# Master.net
KiCad netlist of a schematic drawn in Altium Designer
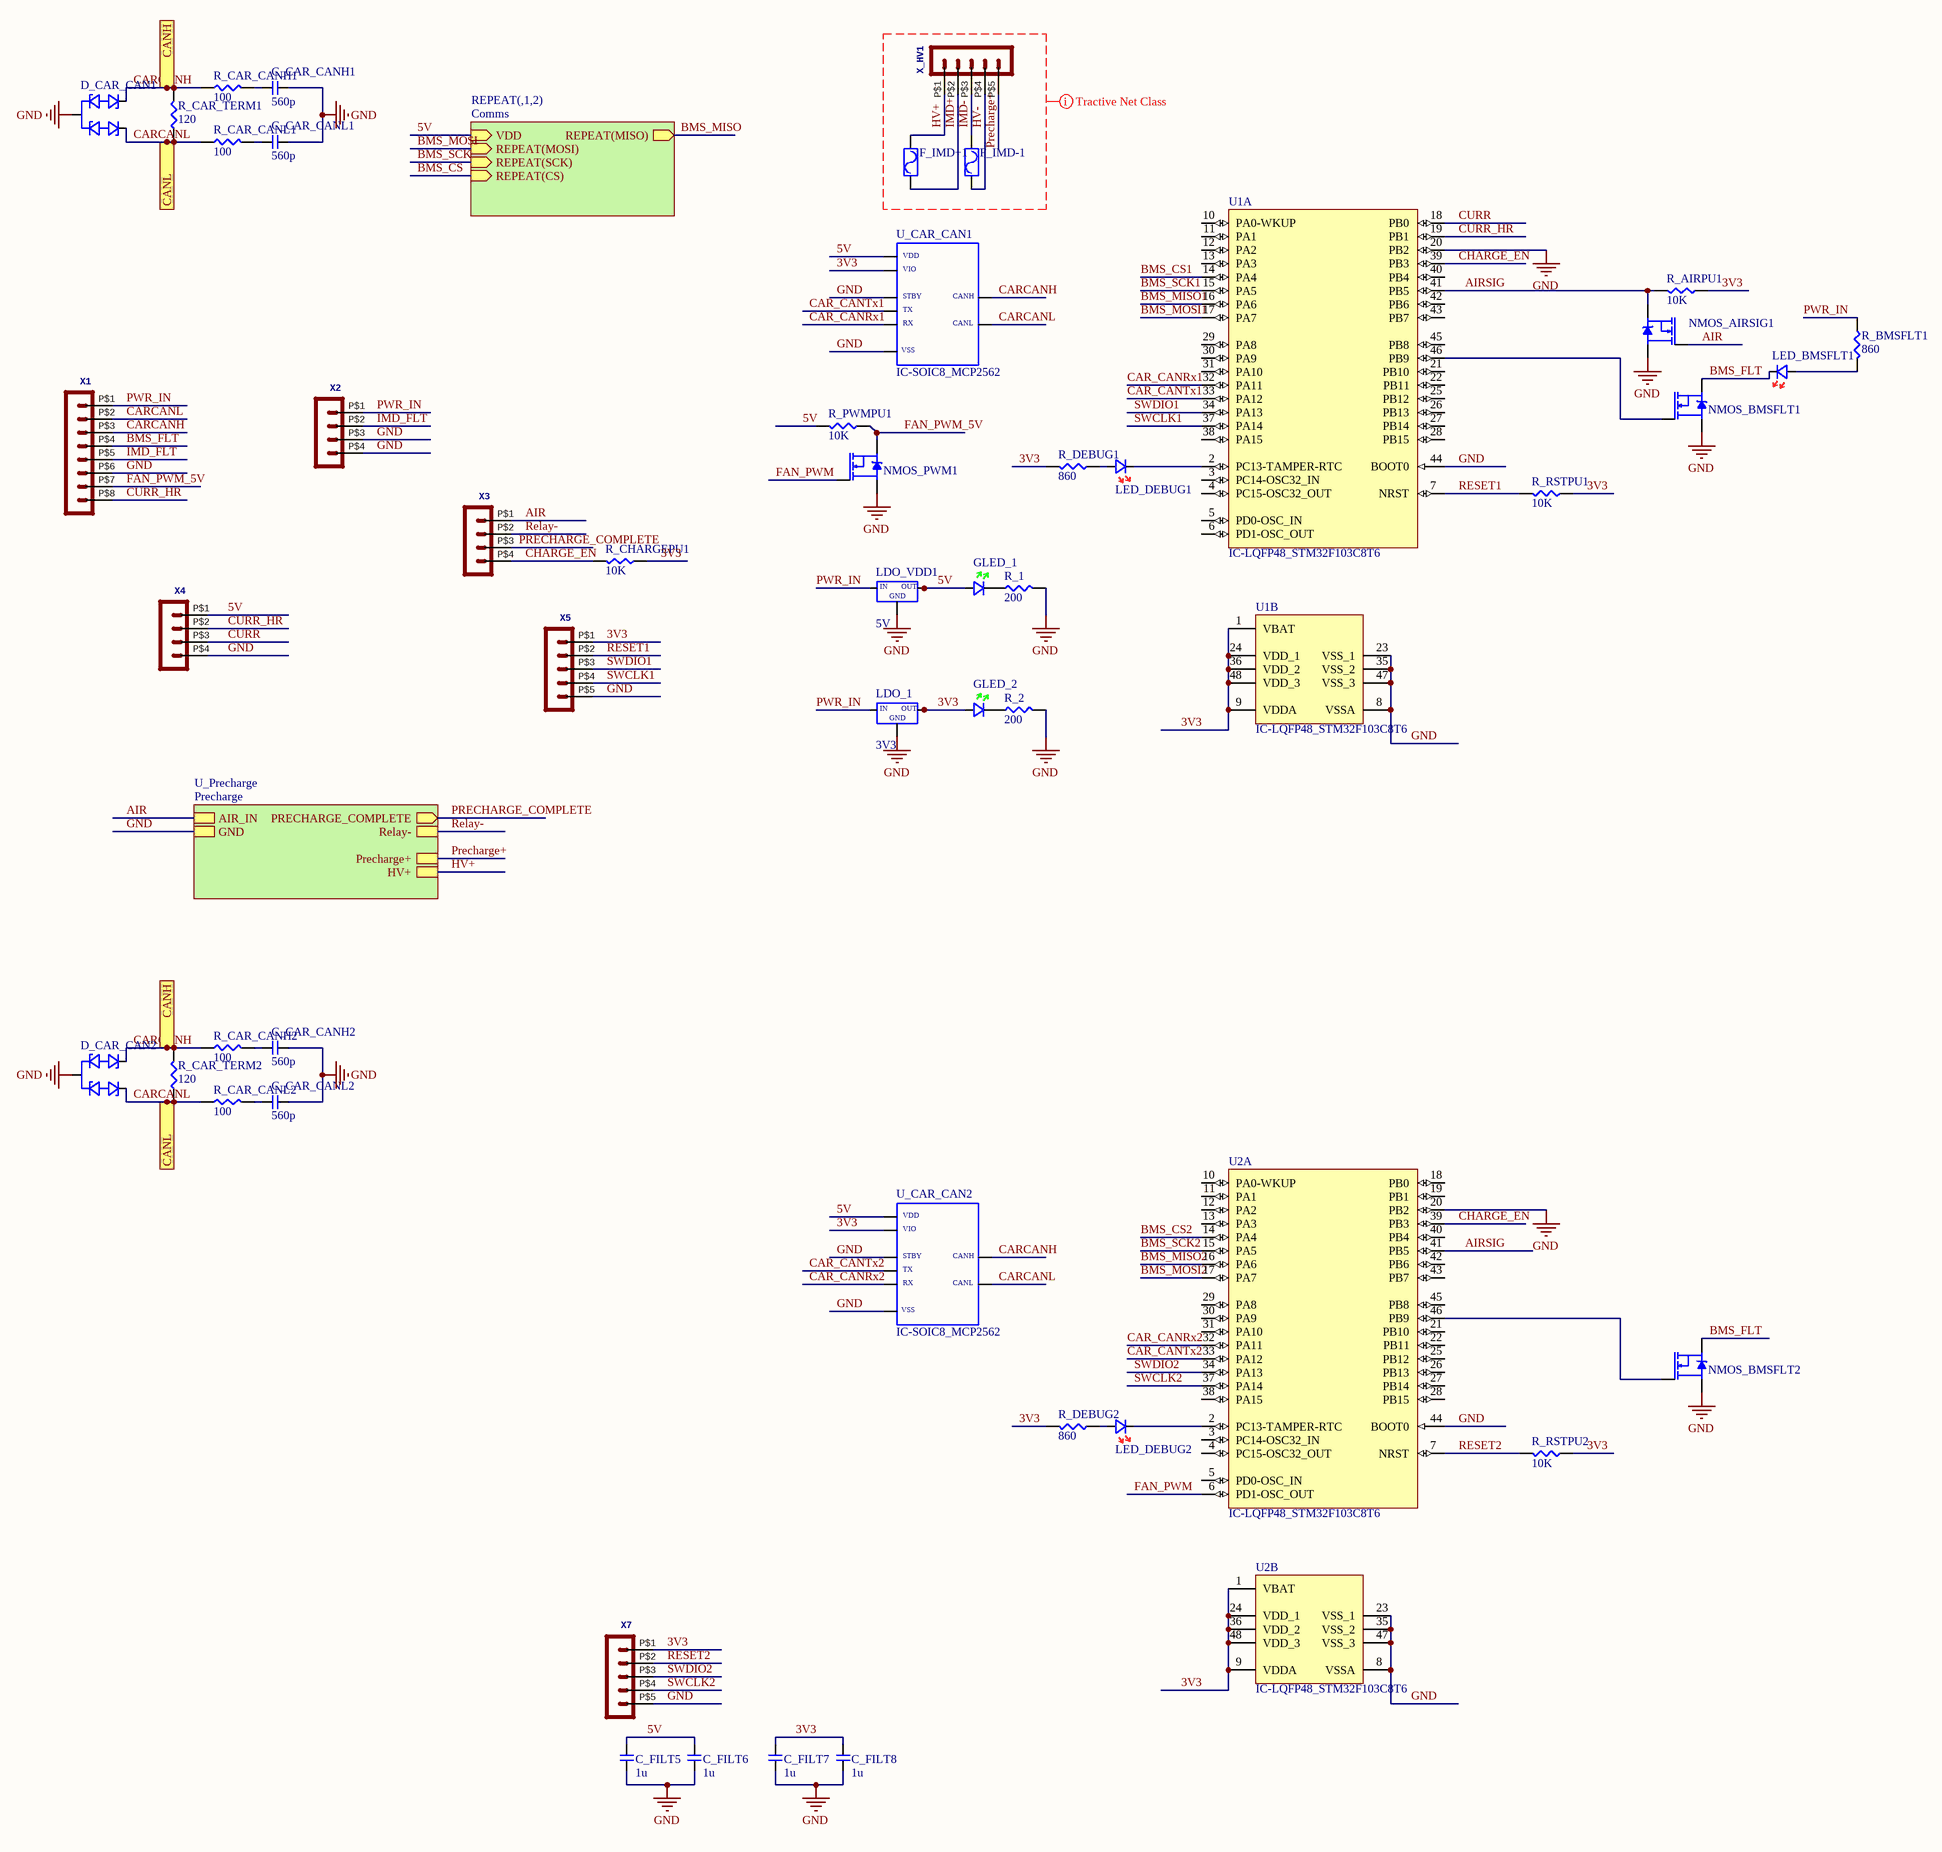
[diagram p0: Master.SchDoc]

(export (version "E")
  (design (tool "Eeschema 10.0.6"))
  (components
    (comp (ref "C_CAR_CANH1")
      (value "560p")
      (footprint "CAP-0603")
      (libsource (lib "altium-import") (part "root_0_CAP-0603_"))
    )
    (comp (ref "C_CAR_CANH2")
      (value "560p")
      (footprint "CAP-0603")
      (libsource (lib "altium-import") (part "root_0_CAP-0603_"))
    )
    (comp (ref "C_CAR_CANL1")
      (value "560p")
      (footprint "CAP-0603")
      (libsource (lib "altium-import") (part "root_0_CAP-0603_"))
    )
    (comp (ref "C_CAR_CANL2")
      (value "560p")
      (footprint "CAP-0603")
      (libsource (lib "altium-import") (part "root_0_CAP-0603_"))
    )
    (comp (ref "C_FILT5")
      (value "1u")
      (footprint "CAP-0603")
      (libsource (lib "altium-import") (part "root_1_CAP-0603_"))
    )
    (comp (ref "C_FILT6")
      (value "1u")
      (footprint "CAP-0603")
      (libsource (lib "altium-import") (part "root_1_CAP-0603_"))
    )
    (comp (ref "C_FILT7")
      (value "1u")
      (footprint "CAP-0603")
      (libsource (lib "altium-import") (part "root_1_CAP-0603_"))
    )
    (comp (ref "C_FILT8")
      (value "1u")
      (footprint "CAP-0603")
      (libsource (lib "altium-import") (part "root_1_CAP-0603_"))
    )
    (comp (ref "D_CAR_CAN1")
      (value "DIODE-SOT23_PESD1CAN")
      (footprint "SOT23")
      (libsource (lib "altium-import") (part "root_0_DIODE-SOT23_PESD1CAN_"))
    )
    (comp (ref "D_CAR_CAN2")
      (value "DIODE-SOT23_PESD1CAN")
      (footprint "SOT23")
      (libsource (lib "altium-import") (part "root_0_DIODE-SOT23_PESD1CAN_"))
    )
    (comp (ref "F_IMD+1")
      (value "FUSE_885")
      (footprint "FUSE_885")
      (libsource (lib "ife19_Elec_Library") (part "FUSE_885"))
    )
    (comp (ref "F_IMD-1")
      (value "FUSE_885")
      (footprint "FUSE_885")
      (libsource (lib "ife19_Elec_Library") (part "FUSE_885"))
    )
    (comp (ref "GLED_1")
      (value "~")
      (footprint "LEDGREEN-0603")
      (libsource (lib "altium-import") (part "root_0_LEDGREEN-0603_"))
    )
    (comp (ref "GLED_2")
      (value "~")
      (footprint "LEDGREEN-0603")
      (libsource (lib "altium-import") (part "root_0_LEDGREEN-0603_"))
    )
    (comp (ref "LDO_1")
      (value "3V3")
      (footprint "SOT223")
      (libsource (lib "altium-import") (part "root_0_LDO-SOT223_SPX1117_"))
    )
    (comp (ref "LDO_VDD1")
      (value "5V")
      (footprint "SOT223")
      (libsource (lib "altium-import") (part "root_0_LDO-SOT223_SPX1117_"))
    )
    (comp (ref "LED_BMSFLT1")
      (value "LEDRED-0603")
      (footprint "LEDRED-0603")
      (libsource (lib "altium-import") (part "root_2_LEDRED-0603_"))
    )
    (comp (ref "LED_DEBUG1")
      (value "LEDRED-0603")
      (footprint "LEDRED-0603")
      (libsource (lib "altium-import") (part "root_2_mirrored_LEDRED-0603_"))
    )
    (comp (ref "LED_DEBUG2")
      (value "LEDRED-0603")
      (footprint "LEDRED-0603")
      (libsource (lib "altium-import") (part "root_2_mirrored_LEDRED-0603_"))
    )
    (comp (ref "NMOS_AIRSIG1")
      (value "NMOS-SOT23")
      (footprint "SOT23")
      (libsource (lib "altium-import") (part "root_0_NMOS-SOT23_"))
    )
    (comp (ref "NMOS_BMSFLT1")
      (value "NMOS-SOT23")
      (footprint "SOT23")
      (libsource (lib "altium-import") (part "root_0_mirrored_NMOS-SOT23_"))
    )
    (comp (ref "NMOS_BMSFLT2")
      (value "NMOS-SOT23")
      (footprint "SOT23")
      (libsource (lib "altium-import") (part "root_0_mirrored_NMOS-SOT23_"))
    )
    (comp (ref "NMOS_PWM1")
      (value "NMOS-SOT23")
      (footprint "SOT23")
      (libsource (lib "altium-import") (part "root_0_mirrored_NMOS-SOT23_"))
    )
    (comp (ref "R_1")
      (value "200")
      (footprint "RES-0603")
      (libsource (lib "altium-import") (part "root_0_RES-0603_"))
    )
    (comp (ref "R_2")
      (value "200")
      (footprint "RES-0603")
      (libsource (lib "altium-import") (part "root_0_RES-0603_"))
    )
    (comp (ref "R_AIRPU1")
      (value "10K")
      (footprint "RES-0603")
      (libsource (lib "altium-import") (part "root_2_RES-0603_"))
    )
    (comp (ref "R_BMSFLT1")
      (value "860")
      (footprint "RES-0603")
      (libsource (lib "altium-import") (part "root_1_mirrored_RES-0603_"))
    )
    (comp (ref "R_CAR_CANH1")
      (value "100")
      (footprint "RES-0603")
      (libsource (lib "altium-import") (part "root_0_RES-0603_"))
    )
    (comp (ref "R_CAR_CANH2")
      (value "100")
      (footprint "RES-0603")
      (libsource (lib "altium-import") (part "root_0_RES-0603_"))
    )
    (comp (ref "R_CAR_CANL1")
      (value "100")
      (footprint "RES-0603")
      (libsource (lib "altium-import") (part "root_0_RES-0603_"))
    )
    (comp (ref "R_CAR_CANL2")
      (value "100")
      (footprint "RES-0603")
      (libsource (lib "altium-import") (part "root_0_RES-0603_"))
    )
    (comp (ref "R_CAR_TERM1")
      (value "120")
      (footprint "RES-0603")
      (libsource (lib "altium-import") (part "root_1_RES-0603_"))
    )
    (comp (ref "R_CAR_TERM2")
      (value "120")
      (footprint "RES-0603")
      (libsource (lib "altium-import") (part "root_1_RES-0603_"))
    )
    (comp (ref "R_CHARGEPU1")
      (value "10K")
      (footprint "RES-0603")
      (libsource (lib "altium-import") (part "root_2_RES-0603_"))
    )
    (comp (ref "R_DEBUG1")
      (value "860")
      (footprint "RES-0603")
      (libsource (lib "altium-import") (part "root_2_RES-0603_"))
    )
    (comp (ref "R_DEBUG2")
      (value "860")
      (footprint "RES-0603")
      (libsource (lib "altium-import") (part "root_2_RES-0603_"))
    )
    (comp (ref "R_PWMPU1")
      (value "10K")
      (footprint "RES-0603")
      (libsource (lib "altium-import") (part "root_2_mirrored_RES-0603_"))
    )
    (comp (ref "R_RSTPU1")
      (value "10K")
      (footprint "RES-0603")
      (libsource (lib "altium-import") (part "root_2_RES-0603_"))
    )
    (comp (ref "R_RSTPU2")
      (value "10K")
      (footprint "RES-0603")
      (libsource (lib "altium-import") (part "root_2_RES-0603_"))
    )
    (comp (ref "U1")
      (value "IC-LQFP48_STM32F103C8T6")
      (footprint "STM-LQFP48_M")
      (fields (field (name "PARTNUMBER") "STM32F103C8T6"))
      (libsource (lib "ife19_Elec_Library") (part "IC-LQFP48_STM32F103C8T6"))
    )
    (comp (ref "U2")
      (value "IC-LQFP48_STM32F103C8T6")
      (footprint "STM-LQFP48_M")
      (fields (field (name "PARTNUMBER") "STM32F103C8T6"))
      (libsource (lib "ife19_Elec_Library") (part "IC-LQFP48_STM32F103C8T6"))
    )
    (comp (ref "U_CAR_CAN1")
      (value "IC-SOIC8_MCP2562")
      (footprint "SOIC8")
      (libsource (lib "altium-import") (part "root_0_IC-SOIC8_MCP2562_"))
    )
    (comp (ref "U_CAR_CAN2")
      (value "IC-SOIC8_MCP2562")
      (footprint "SOIC8")
      (libsource (lib "altium-import") (part "root_0_IC-SOIC8_MCP2562_"))
    )
    (comp (ref "X1")
      (value "Molex - Micro-Fit 3.0 Series connector,  3.00mm (0.118\") pitch header, 8 positions.")
      (footprint "43650-0824")
      (libsource (lib "MOLEX Micro-Fit") (part "HEADER_POS8_?43650-0824"))
    )
    (comp (ref "X2")
      (value "Molex - Micro-Fit 3.0 Series connector,  3.00mm (0.118\") pitch header, 4 positions.")
      (footprint "43650-0424")
      (libsource (lib "ife19_Elec_Conn_Library") (part "POS4_MF43650-0424"))
    )
    (comp (ref "X3")
      (value "Molex - Micro-Fit 3.0 Series connector,  3.00mm (0.118\") pitch header, 4 positions.")
      (footprint "43650-0424")
      (libsource (lib "ife19_Elec_Conn_Library") (part "POS4_MF43650-0424"))
    )
    (comp (ref "X4")
      (value "Molex - Micro-Fit 3.0 Series connector,  3.00mm (0.118\") pitch header, 4 positions.")
      (footprint "43650-0424")
      (libsource (lib "ife19_Elec_Conn_Library") (part "POS4_MF43650-0424"))
    )
    (comp (ref "X5")
      (value "~")
      (footprint "POS5_254MM_MALE")
      (libsource (lib "altium-import") (part "root_0_mirrored_POS5_254MM_MALE_"))
    )
    (comp (ref "X7")
      (value "~")
      (footprint "POS5_254MM_MALE")
      (libsource (lib "altium-import") (part "root_0_mirrored_POS5_254MM_MALE_"))
    )
    (comp (ref "X_HV1")
      (value "Molex - Micro-Fit 3.0 Series connector,  3.00mm (0.118\") pitch header, 5 positions.")
      (footprint "43650-0524")
      (libsource (lib "ife19_Elec_Conn_Library") (part "POS5_MF43650-0524"))
    )
  )
  (nets
    (net (code "1") (name "/3V3") (class "Default")
      (node (ref "C_FILT7") (pin "2") (pinfunction "2_2") (pintype "passive"))
      (node (ref "C_FILT8") (pin "2") (pinfunction "2_2") (pintype "passive"))
      (node (ref "GLED_2") (pin "A") (pinfunction "A_A") (pintype "passive"))
      (node (ref "LDO_1") (pin "2") (pinfunction "2_2") (pintype "passive"))
      (node (ref "LDO_1") (pin "4") (pinfunction "4_4") (pintype "passive"))
      (node (ref "R_AIRPU1") (pin "1") (pinfunction "1_1") (pintype "passive"))
      (node (ref "R_CHARGEPU1") (pin "1") (pinfunction "1_1") (pintype "passive"))
      (node (ref "R_DEBUG1") (pin "2") (pinfunction "2_2") (pintype "passive"))
      (node (ref "R_DEBUG2") (pin "2") (pinfunction "2_2") (pintype "passive"))
      (node (ref "R_RSTPU1") (pin "1") (pinfunction "1_1") (pintype "passive"))
      (node (ref "R_RSTPU2") (pin "1") (pinfunction "1_1") (pintype "passive"))
      (node (ref "U1") (pin "1") (pinfunction "VBAT_1") (pintype "power_in"))
      (node (ref "U1") (pin "24") (pinfunction "VDD_1_24") (pintype "power_in"))
      (node (ref "U1") (pin "36") (pinfunction "VDD_2_36") (pintype "power_in"))
      (node (ref "U1") (pin "48") (pinfunction "VDD_3_48") (pintype "power_in"))
      (node (ref "U1") (pin "9") (pinfunction "VDDA_9") (pintype "power_in"))
      (node (ref "U2") (pin "1") (pinfunction "VBAT_1") (pintype "power_in"))
      (node (ref "U2") (pin "24") (pinfunction "VDD_1_24") (pintype "power_in"))
      (node (ref "U2") (pin "36") (pinfunction "VDD_2_36") (pintype "power_in"))
      (node (ref "U2") (pin "48") (pinfunction "VDD_3_48") (pintype "power_in"))
      (node (ref "U2") (pin "9") (pinfunction "VDDA_9") (pintype "power_in"))
      (node (ref "U_CAR_CAN1") (pin "5") (pinfunction "5_5") (pintype "passive"))
      (node (ref "U_CAR_CAN2") (pin "5") (pinfunction "5_5") (pintype "passive"))
      (node (ref "X5") (pin "P$1") (pinfunction "1_P$1") (pintype "passive"))
      (node (ref "X7") (pin "P$1") (pinfunction "1_P$1") (pintype "passive"))
    )
    (net (code "2") (name "/5V") (class "Default")
      (node (ref "C_FILT5") (pin "2") (pinfunction "2_2") (pintype "passive"))
      (node (ref "C_FILT6") (pin "2") (pinfunction "2_2") (pintype "passive"))
      (node (ref "GLED_1") (pin "A") (pinfunction "A_A") (pintype "passive"))
      (node (ref "LDO_VDD1") (pin "2") (pinfunction "2_2") (pintype "passive"))
      (node (ref "LDO_VDD1") (pin "4") (pinfunction "4_4") (pintype "passive"))
      (node (ref "R_PWMPU1") (pin "1") (pinfunction "1_1") (pintype "passive"))
      (node (ref "U_CAR_CAN1") (pin "3") (pinfunction "3_3") (pintype "passive"))
      (node (ref "U_CAR_CAN2") (pin "3") (pinfunction "3_3") (pintype "passive"))
      (node (ref "X4") (pin "P$1") (pinfunction "1_P$1") (pintype "passive"))
    )
    (net (code "3") (name "/AIR") (class "Default")
      (node (ref "NMOS_AIRSIG1") (pin "1") (pinfunction "G_1") (pintype "passive"))
      (node (ref "X3") (pin "P$1") (pinfunction "1_P$1") (pintype "passive"))
    )
    (net (code "4") (name "/AIRSIG") (class "Default")
      (node (ref "NMOS_AIRSIG1") (pin "3") (pinfunction "D_3") (pintype "passive"))
      (node (ref "R_AIRPU1") (pin "2") (pinfunction "2_2") (pintype "passive"))
      (node (ref "U1") (pin "41") (pinfunction "PB5_41") (pintype "bidirectional"))
      (node (ref "U2") (pin "41") (pinfunction "PB5_41") (pintype "bidirectional"))
    )
    (net (code "6") (name "/BMS_CS1") (class "Default")
      (node (ref "U1") (pin "14") (pinfunction "PA4_14") (pintype "bidirectional"))
    )
    (net (code "7") (name "/BMS_CS2") (class "Default")
      (node (ref "U2") (pin "14") (pinfunction "PA4_14") (pintype "bidirectional"))
    )
    (net (code "8") (name "/BMS_FLT") (class "Default")
      (node (ref "LED_BMSFLT1") (pin "K") (pinfunction "K_K") (pintype "passive"))
      (node (ref "NMOS_BMSFLT1") (pin "3") (pinfunction "D_3") (pintype "passive"))
      (node (ref "NMOS_BMSFLT2") (pin "3") (pinfunction "D_3") (pintype "passive"))
      (node (ref "X1") (pin "P$4") (pinfunction "4_P$4") (pintype "passive"))
    )
    (net (code "10") (name "/BMS_MISO1") (class "Default")
      (node (ref "U1") (pin "16") (pinfunction "PA6_16") (pintype "bidirectional"))
    )
    (net (code "11") (name "/BMS_MISO2") (class "Default")
      (node (ref "U2") (pin "16") (pinfunction "PA6_16") (pintype "bidirectional"))
    )
    (net (code "13") (name "/BMS_MOSI1") (class "Default")
      (node (ref "U1") (pin "17") (pinfunction "PA7_17") (pintype "bidirectional"))
    )
    (net (code "14") (name "/BMS_MOSI2") (class "Default")
      (node (ref "U2") (pin "17") (pinfunction "PA7_17") (pintype "bidirectional"))
    )
    (net (code "16") (name "/BMS_SCK1") (class "Default")
      (node (ref "U1") (pin "15") (pinfunction "PA5_15") (pintype "bidirectional"))
    )
    (net (code "17") (name "/BMS_SCK2") (class "Default")
      (node (ref "U2") (pin "15") (pinfunction "PA5_15") (pintype "bidirectional"))
    )
    (net (code "18") (name "/CARCANH") (class "Default")
      (node (ref "D_CAR_CAN1") (pin "2") (pinfunction "CAN2_2") (pintype "passive"))
      (node (ref "D_CAR_CAN2") (pin "2") (pinfunction "CAN2_2") (pintype "passive"))
      (node (ref "R_CAR_CANH1") (pin "1") (pinfunction "1_1") (pintype "passive"))
      (node (ref "R_CAR_CANH2") (pin "1") (pinfunction "1_1") (pintype "passive"))
      (node (ref "R_CAR_TERM1") (pin "2") (pinfunction "2_2") (pintype "passive"))
      (node (ref "R_CAR_TERM2") (pin "2") (pinfunction "2_2") (pintype "passive"))
      (node (ref "U_CAR_CAN1") (pin "7") (pinfunction "7_7") (pintype "passive"))
      (node (ref "U_CAR_CAN2") (pin "7") (pinfunction "7_7") (pintype "passive"))
      (node (ref "X1") (pin "P$3") (pinfunction "3_P$3") (pintype "passive"))
    )
    (net (code "19") (name "/CARCANL") (class "Default")
      (node (ref "D_CAR_CAN1") (pin "1") (pinfunction "CAN1_1") (pintype "passive"))
      (node (ref "D_CAR_CAN2") (pin "1") (pinfunction "CAN1_1") (pintype "passive"))
      (node (ref "R_CAR_CANL1") (pin "1") (pinfunction "1_1") (pintype "passive"))
      (node (ref "R_CAR_CANL2") (pin "1") (pinfunction "1_1") (pintype "passive"))
      (node (ref "R_CAR_TERM1") (pin "1") (pinfunction "1_1") (pintype "passive"))
      (node (ref "R_CAR_TERM2") (pin "1") (pinfunction "1_1") (pintype "passive"))
      (node (ref "U_CAR_CAN1") (pin "6") (pinfunction "6_6") (pintype "passive"))
      (node (ref "U_CAR_CAN2") (pin "6") (pinfunction "6_6") (pintype "passive"))
      (node (ref "X1") (pin "P$2") (pinfunction "2_P$2") (pintype "passive"))
    )
    (net (code "20") (name "/CAR_CANRx1") (class "Default")
      (node (ref "U1") (pin "32") (pinfunction "PA11_32") (pintype "bidirectional"))
      (node (ref "U_CAR_CAN1") (pin "4") (pinfunction "4_4") (pintype "passive"))
    )
    (net (code "21") (name "/CAR_CANRx2") (class "Default")
      (node (ref "U2") (pin "32") (pinfunction "PA11_32") (pintype "bidirectional"))
      (node (ref "U_CAR_CAN2") (pin "4") (pinfunction "4_4") (pintype "passive"))
    )
    (net (code "22") (name "/CAR_CANTx1") (class "Default")
      (node (ref "U1") (pin "33") (pinfunction "PA12_33") (pintype "bidirectional"))
      (node (ref "U_CAR_CAN1") (pin "1") (pinfunction "1_1") (pintype "passive"))
    )
    (net (code "23") (name "/CAR_CANTx2") (class "Default")
      (node (ref "U2") (pin "33") (pinfunction "PA12_33") (pintype "bidirectional"))
      (node (ref "U_CAR_CAN2") (pin "1") (pinfunction "1_1") (pintype "passive"))
    )
    (net (code "24") (name "/CHARGE_EN") (class "Default")
      (node (ref "R_CHARGEPU1") (pin "2") (pinfunction "2_2") (pintype "passive"))
      (node (ref "U1") (pin "39") (pinfunction "PB3_39") (pintype "bidirectional"))
      (node (ref "U2") (pin "39") (pinfunction "PB3_39") (pintype "bidirectional"))
      (node (ref "X3") (pin "P$4") (pinfunction "4_P$4") (pintype "passive"))
    )
    (net (code "25") (name "/CURR") (class "Default")
      (node (ref "U1") (pin "18") (pinfunction "PB0_18") (pintype "bidirectional"))
      (node (ref "X4") (pin "P$3") (pinfunction "3_P$3") (pintype "passive"))
    )
    (net (code "26") (name "/CURR_HR") (class "Default")
      (node (ref "U1") (pin "19") (pinfunction "PB1_19") (pintype "bidirectional"))
      (node (ref "X1") (pin "P$8") (pinfunction "8_P$8") (pintype "passive"))
      (node (ref "X4") (pin "P$2") (pinfunction "2_P$2") (pintype "passive"))
    )
    (net (code "27") (name "/FAN_PWM") (class "Default")
      (node (ref "NMOS_PWM1") (pin "1") (pinfunction "G_1") (pintype "passive"))
      (node (ref "U2") (pin "6") (pinfunction "PD1-OSC_OUT_6") (pintype "bidirectional"))
    )
    (net (code "28") (name "/FAN_PWM_5V") (class "Default")
      (node (ref "NMOS_PWM1") (pin "3") (pinfunction "D_3") (pintype "passive"))
      (node (ref "R_PWMPU1") (pin "2") (pinfunction "2_2") (pintype "passive"))
      (node (ref "X1") (pin "P$7") (pinfunction "7_P$7") (pintype "passive"))
    )
    (net (code "29") (name "/HV+") (class "Default")
      (node (ref "F_IMD+1") (pin "1") (pinfunction "1_1") (pintype "passive"))
      (node (ref "X_HV1") (pin "P$1") (pinfunction "1_P$1") (pintype "passive"))
    )
    (net (code "30") (name "/HV-") (class "Default")
      (node (ref "F_IMD-1") (pin "2") (pinfunction "2_2") (pintype "passive"))
      (node (ref "X_HV1") (pin "P$4") (pinfunction "4_P$4") (pintype "passive"))
    )
    (net (code "31") (name "/IMD+") (class "Default")
      (node (ref "F_IMD+1") (pin "2") (pinfunction "2_2") (pintype "passive"))
      (node (ref "X_HV1") (pin "P$2") (pinfunction "2_P$2") (pintype "passive"))
    )
    (net (code "32") (name "/IMD-") (class "Default")
      (node (ref "F_IMD-1") (pin "1") (pinfunction "1_1") (pintype "passive"))
      (node (ref "X_HV1") (pin "P$3") (pinfunction "3_P$3") (pintype "passive"))
    )
    (net (code "33") (name "/IMD_FLT") (class "Default")
      (node (ref "X1") (pin "P$5") (pinfunction "5_P$5") (pintype "passive"))
      (node (ref "X2") (pin "P$2") (pinfunction "2_P$2") (pintype "passive"))
    )
    (net (code "34") (name "/PRECHARGE_COMPLETE") (class "Default")
      (node (ref "X3") (pin "P$3") (pinfunction "3_P$3") (pintype "passive"))
    )
    (net (code "35") (name "/PWR_IN") (class "Default")
      (node (ref "LDO_1") (pin "3") (pinfunction "3_3") (pintype "passive"))
      (node (ref "LDO_VDD1") (pin "3") (pinfunction "3_3") (pintype "passive"))
      (node (ref "R_BMSFLT1") (pin "2") (pinfunction "2_2") (pintype "passive"))
      (node (ref "X1") (pin "P$1") (pinfunction "1_P$1") (pintype "passive"))
      (node (ref "X2") (pin "P$1") (pinfunction "1_P$1") (pintype "passive"))
    )
    (net (code "36") (name "/Precharge+") (class "Default")
      (node (ref "X_HV1") (pin "P$5") (pinfunction "5_P$5") (pintype "passive"))
    )
    (net (code "37") (name "/RESET1") (class "Default")
      (node (ref "R_RSTPU1") (pin "2") (pinfunction "2_2") (pintype "passive"))
      (node (ref "U1") (pin "7") (pinfunction "NRST_7") (pintype "bidirectional"))
      (node (ref "X5") (pin "P$2") (pinfunction "2_P$2") (pintype "passive"))
    )
    (net (code "38") (name "/RESET2") (class "Default")
      (node (ref "R_RSTPU2") (pin "2") (pinfunction "2_2") (pintype "passive"))
      (node (ref "U2") (pin "7") (pinfunction "NRST_7") (pintype "bidirectional"))
      (node (ref "X7") (pin "P$2") (pinfunction "2_P$2") (pintype "passive"))
    )
    (net (code "39") (name "/Relay-") (class "Default")
      (node (ref "X3") (pin "P$2") (pinfunction "2_P$2") (pintype "passive"))
    )
    (net (code "40") (name "/SWCLK1") (class "Default")
      (node (ref "U1") (pin "37") (pinfunction "PA14_37") (pintype "bidirectional"))
      (node (ref "X5") (pin "P$4") (pinfunction "4_P$4") (pintype "passive"))
    )
    (net (code "41") (name "/SWCLK2") (class "Default")
      (node (ref "U2") (pin "37") (pinfunction "PA14_37") (pintype "bidirectional"))
      (node (ref "X7") (pin "P$4") (pinfunction "4_P$4") (pintype "passive"))
    )
    (net (code "42") (name "/SWDIO1") (class "Default")
      (node (ref "U1") (pin "34") (pinfunction "PA13_34") (pintype "bidirectional"))
      (node (ref "X5") (pin "P$3") (pinfunction "3_P$3") (pintype "passive"))
    )
    (net (code "43") (name "/SWDIO2") (class "Default")
      (node (ref "U2") (pin "34") (pinfunction "PA13_34") (pintype "bidirectional"))
      (node (ref "X7") (pin "P$3") (pinfunction "3_P$3") (pintype "passive"))
    )
    (net (code "44") (name "GND") (class "Default")
      (node (ref "C_CAR_CANH1") (pin "2") (pinfunction "2_2") (pintype "passive"))
      (node (ref "C_CAR_CANH2") (pin "2") (pinfunction "2_2") (pintype "passive"))
      (node (ref "C_CAR_CANL1") (pin "2") (pinfunction "2_2") (pintype "passive"))
      (node (ref "C_CAR_CANL2") (pin "2") (pinfunction "2_2") (pintype "passive"))
      (node (ref "C_FILT5") (pin "1") (pinfunction "1_1") (pintype "passive"))
      (node (ref "C_FILT6") (pin "1") (pinfunction "1_1") (pintype "passive"))
      (node (ref "C_FILT7") (pin "1") (pinfunction "1_1") (pintype "passive"))
      (node (ref "C_FILT8") (pin "1") (pinfunction "1_1") (pintype "passive"))
      (node (ref "D_CAR_CAN1") (pin "3") (pinfunction "G_3") (pintype "passive"))
      (node (ref "D_CAR_CAN2") (pin "3") (pinfunction "G_3") (pintype "passive"))
      (node (ref "LDO_1") (pin "1") (pinfunction "1_1") (pintype "passive"))
      (node (ref "LDO_VDD1") (pin "1") (pinfunction "1_1") (pintype "passive"))
      (node (ref "NMOS_AIRSIG1") (pin "2") (pinfunction "S_2") (pintype "passive"))
      (node (ref "NMOS_BMSFLT1") (pin "2") (pinfunction "S_2") (pintype "passive"))
      (node (ref "NMOS_BMSFLT2") (pin "2") (pinfunction "S_2") (pintype "passive"))
      (node (ref "NMOS_PWM1") (pin "2") (pinfunction "S_2") (pintype "passive"))
      (node (ref "R_1") (pin "2") (pinfunction "2_2") (pintype "passive"))
      (node (ref "R_2") (pin "2") (pinfunction "2_2") (pintype "passive"))
      (node (ref "U1") (pin "20") (pinfunction "PB2_20") (pintype "bidirectional"))
      (node (ref "U1") (pin "23") (pinfunction "VSS_1_23") (pintype "power_in"))
      (node (ref "U1") (pin "35") (pinfunction "VSS_2_35") (pintype "power_in"))
      (node (ref "U1") (pin "44") (pinfunction "BOOT0_44") (pintype "input"))
      (node (ref "U1") (pin "47") (pinfunction "VSS_3_47") (pintype "power_in"))
      (node (ref "U1") (pin "8") (pinfunction "VSSA_8") (pintype "power_in"))
      (node (ref "U2") (pin "20") (pinfunction "PB2_20") (pintype "bidirectional"))
      (node (ref "U2") (pin "23") (pinfunction "VSS_1_23") (pintype "power_in"))
      (node (ref "U2") (pin "35") (pinfunction "VSS_2_35") (pintype "power_in"))
      (node (ref "U2") (pin "44") (pinfunction "BOOT0_44") (pintype "input"))
      (node (ref "U2") (pin "47") (pinfunction "VSS_3_47") (pintype "power_in"))
      (node (ref "U2") (pin "8") (pinfunction "VSSA_8") (pintype "power_in"))
      (node (ref "U_CAR_CAN1") (pin "2") (pinfunction "2_2") (pintype "passive"))
      (node (ref "U_CAR_CAN1") (pin "8") (pinfunction "8_8") (pintype "passive"))
      (node (ref "U_CAR_CAN2") (pin "2") (pinfunction "2_2") (pintype "passive"))
      (node (ref "U_CAR_CAN2") (pin "8") (pinfunction "8_8") (pintype "passive"))
      (node (ref "X1") (pin "P$6") (pinfunction "6_P$6") (pintype "passive"))
      (node (ref "X2") (pin "P$3") (pinfunction "3_P$3") (pintype "passive"))
      (node (ref "X2") (pin "P$4") (pinfunction "4_P$4") (pintype "passive"))
      (node (ref "X4") (pin "P$4") (pinfunction "4_P$4") (pintype "passive"))
      (node (ref "X5") (pin "P$5") (pinfunction "5_P$5") (pintype "passive"))
      (node (ref "X7") (pin "P$5") (pinfunction "5_P$5") (pintype "passive"))
    )
    (net (code "45") (name "Net-(C_CAR_CANH1-Pad1)") (class "Default")
      (node (ref "C_CAR_CANH1") (pin "1") (pinfunction "1_1") (pintype "passive"))
      (node (ref "R_CAR_CANH1") (pin "2") (pinfunction "2_2") (pintype "passive"))
    )
    (net (code "46") (name "Net-(C_CAR_CANH2-Pad1)") (class "Default")
      (node (ref "C_CAR_CANH2") (pin "1") (pinfunction "1_1") (pintype "passive"))
      (node (ref "R_CAR_CANH2") (pin "2") (pinfunction "2_2") (pintype "passive"))
    )
    (net (code "47") (name "Net-(C_CAR_CANL1-Pad1)") (class "Default")
      (node (ref "C_CAR_CANL1") (pin "1") (pinfunction "1_1") (pintype "passive"))
      (node (ref "R_CAR_CANL1") (pin "2") (pinfunction "2_2") (pintype "passive"))
    )
    (net (code "48") (name "Net-(C_CAR_CANL2-Pad1)") (class "Default")
      (node (ref "C_CAR_CANL2") (pin "1") (pinfunction "1_1") (pintype "passive"))
      (node (ref "R_CAR_CANL2") (pin "2") (pinfunction "2_2") (pintype "passive"))
    )
    (net (code "49") (name "Net-(GLED_1-PadK)") (class "Default")
      (node (ref "GLED_1") (pin "K") (pinfunction "K_K") (pintype "passive"))
      (node (ref "R_1") (pin "1") (pinfunction "1_1") (pintype "passive"))
    )
    (net (code "50") (name "Net-(GLED_2-PadK)") (class "Default")
      (node (ref "GLED_2") (pin "K") (pinfunction "K_K") (pintype "passive"))
      (node (ref "R_2") (pin "1") (pinfunction "1_1") (pintype "passive"))
    )
    (net (code "51") (name "Net-(LED_BMSFLT1-PadA)") (class "Default")
      (node (ref "LED_BMSFLT1") (pin "A") (pinfunction "A_A") (pintype "passive"))
      (node (ref "R_BMSFLT1") (pin "1") (pinfunction "1_1") (pintype "passive"))
    )
    (net (code "52") (name "Net-(LED_DEBUG1-PadA)") (class "Default")
      (node (ref "LED_DEBUG1") (pin "A") (pinfunction "A_A") (pintype "passive"))
      (node (ref "R_DEBUG1") (pin "1") (pinfunction "1_1") (pintype "passive"))
    )
    (net (code "53") (name "Net-(LED_DEBUG2-PadA)") (class "Default")
      (node (ref "LED_DEBUG2") (pin "A") (pinfunction "A_A") (pintype "passive"))
      (node (ref "R_DEBUG2") (pin "1") (pinfunction "1_1") (pintype "passive"))
    )
    (net (code "54") (name "Net-(NMOS_BMSFLT1-G)") (class "Default")
      (node (ref "NMOS_BMSFLT1") (pin "1") (pinfunction "G_1") (pintype "passive"))
      (node (ref "U1") (pin "46") (pinfunction "PB9_46") (pintype "bidirectional"))
    )
    (net (code "55") (name "Net-(NMOS_BMSFLT2-G)") (class "Default")
      (node (ref "NMOS_BMSFLT2") (pin "1") (pinfunction "G_1") (pintype "passive"))
      (node (ref "U2") (pin "46") (pinfunction "PB9_46") (pintype "bidirectional"))
    )
    (net (code "56") (name "Net-(U1A-PC13-TAMPER-RTC)") (class "Default")
      (node (ref "LED_DEBUG1") (pin "K") (pinfunction "K_K") (pintype "passive"))
      (node (ref "U1") (pin "2") (pinfunction "PC13-TAMPER-RTC_2") (pintype "bidirectional"))
    )
    (net (code "57") (name "Net-(U2A-PC13-TAMPER-RTC)") (class "Default")
      (node (ref "LED_DEBUG2") (pin "K") (pinfunction "K_K") (pintype "passive"))
      (node (ref "U2") (pin "2") (pinfunction "PC13-TAMPER-RTC_2") (pintype "bidirectional"))
    )
    (net (code "58") (name "unconnected-(U1A-PA0-WKUP-Pad10)") (class "Default")
      (node (ref "U1") (pin "10") (pinfunction "PA0-WKUP_10") (pintype "bidirectional"))
    )
    (net (code "59") (name "unconnected-(U1A-PA1-Pad11)") (class "Default")
      (node (ref "U1") (pin "11") (pinfunction "PA1_11") (pintype "bidirectional"))
    )
    (net (code "60") (name "unconnected-(U1A-PA2-Pad12)") (class "Default")
      (node (ref "U1") (pin "12") (pinfunction "PA2_12") (pintype "bidirectional"))
    )
    (net (code "61") (name "unconnected-(U1A-PA3-Pad13)") (class "Default")
      (node (ref "U1") (pin "13") (pinfunction "PA3_13") (pintype "bidirectional"))
    )
    (net (code "62") (name "unconnected-(U1A-PA8-Pad29)") (class "Default")
      (node (ref "U1") (pin "29") (pinfunction "PA8_29") (pintype "bidirectional"))
    )
    (net (code "63") (name "unconnected-(U1A-PA9-Pad30)") (class "Default")
      (node (ref "U1") (pin "30") (pinfunction "PA9_30") (pintype "bidirectional"))
    )
    (net (code "64") (name "unconnected-(U1A-PA10-Pad31)") (class "Default")
      (node (ref "U1") (pin "31") (pinfunction "PA10_31") (pintype "bidirectional"))
    )
    (net (code "65") (name "unconnected-(U1A-PA15-Pad38)") (class "Default")
      (node (ref "U1") (pin "38") (pinfunction "PA15_38") (pintype "bidirectional"))
    )
    (net (code "66") (name "unconnected-(U1A-PB4-Pad40)") (class "Default")
      (node (ref "U1") (pin "40") (pinfunction "PB4_40") (pintype "bidirectional"))
    )
    (net (code "67") (name "unconnected-(U1A-PB6-Pad42)") (class "Default")
      (node (ref "U1") (pin "42") (pinfunction "PB6_42") (pintype "bidirectional"))
    )
    (net (code "68") (name "unconnected-(U1A-PB7-Pad43)") (class "Default")
      (node (ref "U1") (pin "43") (pinfunction "PB7_43") (pintype "bidirectional"))
    )
    (net (code "69") (name "unconnected-(U1A-PB8-Pad45)") (class "Default")
      (node (ref "U1") (pin "45") (pinfunction "PB8_45") (pintype "bidirectional"))
    )
    (net (code "70") (name "unconnected-(U1A-PB10-Pad21)") (class "Default")
      (node (ref "U1") (pin "21") (pinfunction "PB10_21") (pintype "bidirectional"))
    )
    (net (code "71") (name "unconnected-(U1A-PB11-Pad22)") (class "Default")
      (node (ref "U1") (pin "22") (pinfunction "PB11_22") (pintype "bidirectional"))
    )
    (net (code "72") (name "unconnected-(U1A-PB12-Pad25)") (class "Default")
      (node (ref "U1") (pin "25") (pinfunction "PB12_25") (pintype "bidirectional"))
    )
    (net (code "73") (name "unconnected-(U1A-PB13-Pad26)") (class "Default")
      (node (ref "U1") (pin "26") (pinfunction "PB13_26") (pintype "bidirectional"))
    )
    (net (code "74") (name "unconnected-(U1A-PB14-Pad27)") (class "Default")
      (node (ref "U1") (pin "27") (pinfunction "PB14_27") (pintype "bidirectional"))
    )
    (net (code "75") (name "unconnected-(U1A-PB15-Pad28)") (class "Default")
      (node (ref "U1") (pin "28") (pinfunction "PB15_28") (pintype "bidirectional"))
    )
    (net (code "76") (name "unconnected-(U1A-PC14-OSC32_IN-Pad3)") (class "Default")
      (node (ref "U1") (pin "3") (pinfunction "PC14-OSC32_IN_3") (pintype "bidirectional"))
    )
    (net (code "77") (name "unconnected-(U1A-PC15-OSC32_OUT-Pad4)") (class "Default")
      (node (ref "U1") (pin "4") (pinfunction "PC15-OSC32_OUT_4") (pintype "bidirectional"))
    )
    (net (code "78") (name "unconnected-(U1A-PD0-OSC_IN-Pad5)") (class "Default")
      (node (ref "U1") (pin "5") (pinfunction "PD0-OSC_IN_5") (pintype "bidirectional"))
    )
    (net (code "79") (name "unconnected-(U1A-PD1-OSC_OUT-Pad6)") (class "Default")
      (node (ref "U1") (pin "6") (pinfunction "PD1-OSC_OUT_6") (pintype "bidirectional"))
    )
    (net (code "80") (name "unconnected-(U2A-PA0-WKUP-Pad10)") (class "Default")
      (node (ref "U2") (pin "10") (pinfunction "PA0-WKUP_10") (pintype "bidirectional"))
    )
    (net (code "81") (name "unconnected-(U2A-PA1-Pad11)") (class "Default")
      (node (ref "U2") (pin "11") (pinfunction "PA1_11") (pintype "bidirectional"))
    )
    (net (code "82") (name "unconnected-(U2A-PA2-Pad12)") (class "Default")
      (node (ref "U2") (pin "12") (pinfunction "PA2_12") (pintype "bidirectional"))
    )
    (net (code "83") (name "unconnected-(U2A-PA3-Pad13)") (class "Default")
      (node (ref "U2") (pin "13") (pinfunction "PA3_13") (pintype "bidirectional"))
    )
    (net (code "84") (name "unconnected-(U2A-PA8-Pad29)") (class "Default")
      (node (ref "U2") (pin "29") (pinfunction "PA8_29") (pintype "bidirectional"))
    )
    (net (code "85") (name "unconnected-(U2A-PA9-Pad30)") (class "Default")
      (node (ref "U2") (pin "30") (pinfunction "PA9_30") (pintype "bidirectional"))
    )
    (net (code "86") (name "unconnected-(U2A-PA10-Pad31)") (class "Default")
      (node (ref "U2") (pin "31") (pinfunction "PA10_31") (pintype "bidirectional"))
    )
    (net (code "87") (name "unconnected-(U2A-PA15-Pad38)") (class "Default")
      (node (ref "U2") (pin "38") (pinfunction "PA15_38") (pintype "bidirectional"))
    )
    (net (code "88") (name "unconnected-(U2A-PB0-Pad18)") (class "Default")
      (node (ref "U2") (pin "18") (pinfunction "PB0_18") (pintype "bidirectional"))
    )
    (net (code "89") (name "unconnected-(U2A-PB1-Pad19)") (class "Default")
      (node (ref "U2") (pin "19") (pinfunction "PB1_19") (pintype "bidirectional"))
    )
    (net (code "90") (name "unconnected-(U2A-PB4-Pad40)") (class "Default")
      (node (ref "U2") (pin "40") (pinfunction "PB4_40") (pintype "bidirectional"))
    )
    (net (code "91") (name "unconnected-(U2A-PB6-Pad42)") (class "Default")
      (node (ref "U2") (pin "42") (pinfunction "PB6_42") (pintype "bidirectional"))
    )
    (net (code "92") (name "unconnected-(U2A-PB7-Pad43)") (class "Default")
      (node (ref "U2") (pin "43") (pinfunction "PB7_43") (pintype "bidirectional"))
    )
    (net (code "93") (name "unconnected-(U2A-PB8-Pad45)") (class "Default")
      (node (ref "U2") (pin "45") (pinfunction "PB8_45") (pintype "bidirectional"))
    )
    (net (code "94") (name "unconnected-(U2A-PB10-Pad21)") (class "Default")
      (node (ref "U2") (pin "21") (pinfunction "PB10_21") (pintype "bidirectional"))
    )
    (net (code "95") (name "unconnected-(U2A-PB11-Pad22)") (class "Default")
      (node (ref "U2") (pin "22") (pinfunction "PB11_22") (pintype "bidirectional"))
    )
    (net (code "96") (name "unconnected-(U2A-PB12-Pad25)") (class "Default")
      (node (ref "U2") (pin "25") (pinfunction "PB12_25") (pintype "bidirectional"))
    )
    (net (code "97") (name "unconnected-(U2A-PB13-Pad26)") (class "Default")
      (node (ref "U2") (pin "26") (pinfunction "PB13_26") (pintype "bidirectional"))
    )
    (net (code "98") (name "unconnected-(U2A-PB14-Pad27)") (class "Default")
      (node (ref "U2") (pin "27") (pinfunction "PB14_27") (pintype "bidirectional"))
    )
    (net (code "99") (name "unconnected-(U2A-PB15-Pad28)") (class "Default")
      (node (ref "U2") (pin "28") (pinfunction "PB15_28") (pintype "bidirectional"))
    )
    (net (code "100") (name "unconnected-(U2A-PC14-OSC32_IN-Pad3)") (class "Default")
      (node (ref "U2") (pin "3") (pinfunction "PC14-OSC32_IN_3") (pintype "bidirectional"))
    )
    (net (code "101") (name "unconnected-(U2A-PC15-OSC32_OUT-Pad4)") (class "Default")
      (node (ref "U2") (pin "4") (pinfunction "PC15-OSC32_OUT_4") (pintype "bidirectional"))
    )
    (net (code "102") (name "unconnected-(U2A-PD0-OSC_IN-Pad5)") (class "Default")
      (node (ref "U2") (pin "5") (pinfunction "PD0-OSC_IN_5") (pintype "bidirectional"))
    )
  )
)
